# LTE_UART_USB_adapter.net
KiCad netlist of a schematic drawn in Altium Designer
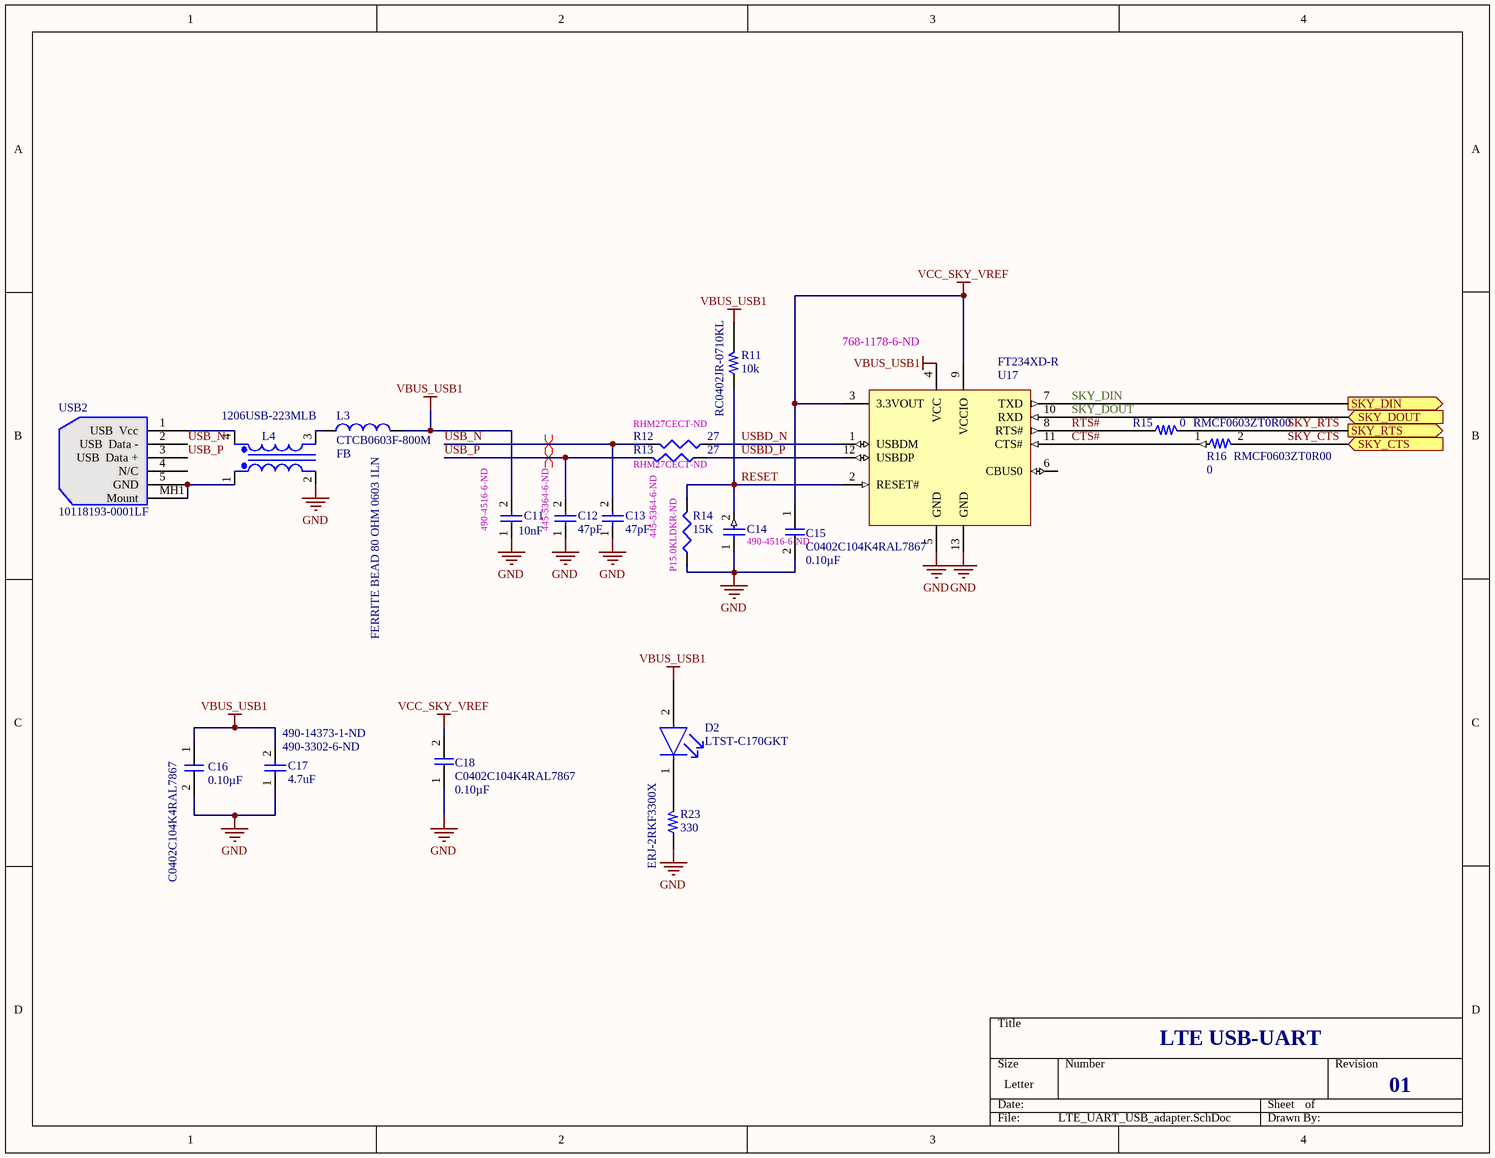
[diagram p0: LTE_UART_USB_adapter.SchDoc]

(export (version "E")
  (design (tool "Eeschema 10.0.6"))
  (components
    (comp (ref "C11")
      (value "GRM155R71H103KA88D")
      (footprint "SMD CAP 1005")
      (description "10000 pF ±10% 50V Ceramic Capacitor X7R 0402 (1005 Metric)")
      (fields
        (field (name "CAPACITANCE") "10nF")
        (field (name "DIGI-KEY PART NUMBER") "490-4516-1-ND")
        (field (name "MANUFACTURER") "Murata Electronics North America")
        (field (name "SUPPLIER PART NUMBER 1") "490-4516-6-ND")
      )
      (libsource (lib "TempProbe") (part "Cap Semi"))
    )
    (comp (ref "C12")
      (value "C1005C0G1H470G050BA")
      (footprint "SMD CAP 1005")
      (description "47 pF ±2% 50V Ceramic Capacitor C0G, NP0 0402 (1005 Metric)")
      (fields
        (field (name "CAPACITANCE") "47pF")
        (field (name "DIGI-KEY PART NUMBER") "445-5364-1-ND")
        (field (name "MANUFACTURER") "TDK Corporation")
        (field (name "SUPPLIER PART NUMBER 1") "445-5364-6-ND")
      )
      (libsource (lib "TempProbe") (part "Cap Semi"))
    )
    (comp (ref "C13")
      (value "C1005C0G1H470G050BA")
      (footprint "SMD CAP 1005")
      (description "47 pF ±2% 50V Ceramic Capacitor C0G, NP0 0402 (1005 Metric)")
      (fields
        (field (name "CAPACITANCE") "47pF")
        (field (name "DIGI-KEY PART NUMBER") "445-5364-1-ND")
        (field (name "MANUFACTURER") "TDK Corporation")
        (field (name "SUPPLIER PART NUMBER 1") "445-5364-6-ND")
      )
      (libsource (lib "TempProbe") (part "Cap Semi"))
    )
    (comp (ref "C14")
      (value "GRM155R71H103KA88D")
      (footprint "SMD CAP 1005")
      (description "10000 pF ±10% 50V Ceramic Capacitor X7R 0402 (1005 Metric)")
      (fields
        (field (name "DIGI-KEY PART NUMBER") "490-4516-1-ND")
        (field (name "MANUFACTURER") "Murata Electronics North America")
        (field (name "SUPPLIER PART NUMBER 1") "490-4516-6-ND")
      )
      (libsource (lib "TempProbe") (part "Cap Semi"))
    )
    (comp (ref "C15")
      (value "C0402C104K4RAL7867")
      (footprint "Passives:SMD CAP 1005")
      (description "0.1 µF ±10% 16V Ceramic Capacitor X7R 0402 (1005 Metric)")
      (fields
        (field (name "TOLERANCE") "±10%")
        (field (name "CAPACITANCE") "0.10µF")
        (field (name "PART_NUMBER") "1000742")
      )
      (libsource (lib "AltiumProductionDatabase") (part "C, 0.1 uF, 16V, 10%, X7R, 0402 CER"))
    )
    (comp (ref "C16")
      (value "C0402C104K4RAL7867")
      (footprint "Passives:SMD CAP 1005")
      (description "0.1 µF ±10% 16V Ceramic Capacitor X7R 0402 (1005 Metric)")
      (fields
        (field (name "TOLERANCE") "±10%")
        (field (name "CAPACITANCE") "0.10µF")
        (field (name "PART_NUMBER") "1000742")
      )
      (libsource (lib "AltiumProductionDatabase") (part "C, 0.1 uF, 16V, 10%, X7R, 0402 CER"))
    )
    (comp (ref "C17")
      (value "GRM188R61A475KAAJD")
      (footprint "CAPC1608M")
      (description "4.7 µF ±10% 10V Ceramic Capacitor X5R 0603 (1608 Metric)")
      (fields
        (field (name "CAPACITANCE") "4.7uF")
        (field (name "DIGI-KEY PART NUMBER") "490-14373-1-ND")
        (field (name "MANUFACTURER") "Murata Electronics North America")
        (field (name "SUPPLIER PART NUMBER 1") "490-3302-6-ND")
        (field (name "SUPPLIER PART NUMBER 2") "490-14373-1-ND")
      )
      (libsource (lib "TempProbe") (part "Cap Semi"))
    )
    (comp (ref "C18")
      (value "C0402C104K4RAL7867")
      (footprint "Passives:SMD CAP 1005")
      (description "0.1 µF ±10% 16V Ceramic Capacitor X7R 0402 (1005 Metric)")
      (fields
        (field (name "TOLERANCE") "±10%")
        (field (name "CAPACITANCE") "0.10µF")
        (field (name "PART_NUMBER") "1000742")
      )
      (libsource (lib "AltiumProductionDatabase") (part "C, 0.1 uF, 16V, 10%, X7R, 0402 CER"))
    )
    (comp (ref "D2")
      (value "LTST-C170GKT")
      (footprint "FP-LTST-C170GKT-MFG")
      (description "Green 569nm LED Indication - Discrete 2.1V 0805 (2012 Metric)")
      (fields (field (name "VOLTAGE") "5V") (field (name "DIGI-KEY PART NUMBER") "160-1179-1-ND"))
      (libsource (lib "Altium Content Vault") (part "8706943c75ba83719d021d2fdc84c58"))
    )
    (comp (ref "L3")
      (value "CTCB0603F-800M")
      (footprint "INDC1608M")
      (description "80 Ohms @ 100 MHz 1 Ferrite Bead 0603 (1608 Metric) 600mA 100mOhm")
      (fields
        (field (name "ALTIUM_VALUE") "FB")
        (field (name "DIGI-KEY PART NUMBER") "4161-CTCB0603F-800M-ND")
        (field (name "MANUFACTURER") "Central Technologies")
        (field (name "DESC") "FERRITE BEAD 80 OHM 0603 1LN")
        (field (name "PUBLISHER") "Altium Limited")
      )
      (libsource (lib "Miscellaneous Devices") (part "Inductor"))
    )
    (comp (ref "L4")
      (value "1206USB-223MLB")
      (footprint "1206USB-223MLB")
      (description "Common Mode Chokes / Filters")
      (fields (field (name "MANUFACTURER") "Coilcraft") (field (name "PUBLISHER") "Altium Limited"))
      (libsource (lib "Miscellaneous Devices") (part "Trans Ideal"))
    )
    (comp (ref "R11")
      (value "RC0402JR-0710KL")
      (footprint "SMD RES 1005")
      (description "10 kOhms ±5% 0.063W, 1/16W Chip Resistor 0402 (1005 Metric) Moisture Resistant Thick Film")
      (fields
        (field (name "PART_NUMBER") "RC0402JR-0710KL")
        (field (name "RESISTANCE_OHMS") "10k")
        (field (name "POWER") "0.063W, 1/16W")
        (field (name "TOLERANCE") "±1%")
      )
      (libsource (lib "AltiumProductionDatabase") (part "R, 10K, 1%, 1/16W,  0402"))
    )
    (comp (ref "R12")
      (value "27")
      (footprint "SMD RES 1005")
      (description "RES SMD 27 OHM 5% 1/16W 0402")
      (fields
        (field (name "DIGI-KEY PART NUMBER") "RHM27CECT-ND")
        (field (name "MANUFACTURER") "Rohm Semiconductor")
        (field (name "SUPPLIER PART NUMBER 1") "RHM27CECT-ND")
        (field (name "PUBLISHER") "Altium Limited")
      )
      (libsource (lib "Miscellaneous Devices") (part "Res3"))
    )
    (comp (ref "R13")
      (value "27")
      (footprint "SMD RES 1005")
      (description "RES SMD 27 OHM 5% 1/16W 0402")
      (fields
        (field (name "DIGI-KEY PART NUMBER") "RHM27CECT-ND")
        (field (name "MANUFACTURER") "Rohm Semiconductor")
        (field (name "SUPPLIER PART NUMBER 1") "RHM27CECT-ND")
        (field (name "PUBLISHER") "Altium Limited")
      )
      (libsource (lib "Miscellaneous Devices") (part "Res3"))
    )
    (comp (ref "R14")
      (value "15K")
      (footprint "SMD RES 1005")
      (description "RES SMD 15K OHM 1% 1/10W 0402")
      (fields
        (field (name "DIGI-KEY PART NUMBER") "P15.0KLCT-ND")
        (field (name "MANUFACTURER") "Panasonic Electronic Components")
        (field (name "SUPPLIER PART NUMBER 1") "P15.0KLDKR-ND")
        (field (name "PUBLISHER") "Altium Limited")
      )
      (libsource (lib "Miscellaneous Devices") (part "Res3"))
    )
    (comp (ref "R15")
      (value "RMCF0603ZT0R00")
      (footprint "RESC1608M")
      (description "0 Ohms Jumper Chip Resistor 0603 (1608 Metric) Automotive AEC-Q200 Thick Film")
      (fields
        (field (name "PART_NUMBER") "RMCF0603ZT0R00")
        (field (name "RESISTANCE") "0")
        (field (name "POWER") "0.25W, 1/4W")
        (field (name "TOLERANCE") "±1%")
      )
      (libsource (lib "") (part "R, 0.1, 1%, 1/4W, 0603_1"))
    )
    (comp (ref "R16")
      (value "RMCF0603ZT0R00")
      (footprint "RESC1608M")
      (description "0 Ohms Jumper Chip Resistor 0603 (1608 Metric) Automotive AEC-Q200 Thick Film")
      (fields
        (field (name "PART_NUMBER") "RMCF0603ZT0R00")
        (field (name "RESISTANCE") "0")
        (field (name "POWER") "0.25W, 1/4W")
        (field (name "TOLERANCE") "±1%")
      )
      (libsource (lib "AltiumProductionDatabase") (part "R, 0.1, 1%, 1/4W, 0603"))
    )
    (comp (ref "R23")
      (value "ERJ-2RKF3300X")
      (footprint "SMD RES 1005")
      (description "330 Ohms ±1% 0.1W, 1/10W Chip Resistor 0402 (1005 Metric) Automotive AEC-Q200 Thick Film")
      (fields
        (field (name "PART_NUMBER") "1001162")
        (field (name "RESISTANCE") "330")
        (field (name "POWER") "0.1W, 1/10W")
      )
      (libsource (lib "AltiumProductionDatabase") (part "R, 330, 1%, 1/10W, 0402"))
    )
    (comp (ref "U17")
      (value "FT234XD-R")
      (footprint "DFN-12_V")
      (description "IC USB SERIAL BASIC UART 12DFN")
      (fields
        (field (name "MANUFACTURER") "FTDI, Future Technology Devices International Ltd")
        (field (name "DIGI-KEY PART NUMBER") "768-1178-1-ND")
        (field (name "SUPPLIER PART NUMBER 1") "768-1178-6-ND")
      )
      (libsource (lib "Altium Content Vault") (part "CMP-0248-00027-1"))
    )
    (comp (ref "USB2")
      (value "10118193-0001LF")
      (footprint "10118193-0001LF Rev01")
      (description "USB - micro B USB 2.0 Receptacle Connector 5 Position Surface Mount, Right Angle, Horizontal")
      (fields (field (name "MANUFACTURER") "FCI") (field (name "DIGI-KEY PART NUMBER") "609-4616-1-ND"))
      (libsource (lib "USB") (part "USB mini"))
    )
  )
  (nets
    (net (code "1") (name "/CTS#") (class "Default")
      (node (ref "R16") (pin "1") (pinfunction "1_1") (pintype "output"))
      (node (ref "U17") (pin "11") (pinfunction "CTS#_11") (pintype "input"))
    )
    (net (code "2") (name "/RESET") (class "Default")
      (node (ref "C14") (pin "2") (pinfunction "2_2") (pintype "passive"))
      (node (ref "R11") (pin "1") (pinfunction "1_1") (pintype "passive"))
      (node (ref "R14") (pin "2") (pinfunction "2_2") (pintype "passive"))
      (node (ref "U17") (pin "2") (pinfunction "RESET#_2") (pintype "input"))
    )
    (net (code "3") (name "/RTS#") (class "Default")
      (node (ref "R15") (pin "1") (pinfunction "1_1") (pintype "passive"))
      (node (ref "U17") (pin "8") (pinfunction "RTS#_8") (pintype "output"))
    )
    (net (code "4") (name "/SKY_CTS") (class "Default")
      (node (ref "R16") (pin "2") (pinfunction "2_2") (pintype "passive"))
    )
    (net (code "5") (name "/SKY_DIN") (class "Default")
      (node (ref "U17") (pin "7") (pinfunction "TXD_7") (pintype "output"))
    )
    (net (code "6") (name "/SKY_DOUT") (class "Default")
      (node (ref "U17") (pin "10") (pinfunction "RXD_10") (pintype "input"))
    )
    (net (code "7") (name "/SKY_RTS") (class "Default")
      (node (ref "R15") (pin "2") (pinfunction "2_2") (pintype "passive"))
    )
    (net (code "8") (name "/USBD_N") (class "Default")
      (node (ref "R12") (pin "1") (pinfunction "1_1") (pintype "passive"))
      (node (ref "U17") (pin "1") (pinfunction "USBDM_1") (pintype "bidirectional"))
    )
    (net (code "9") (name "/USBD_P") (class "Default")
      (node (ref "R13") (pin "1") (pinfunction "1_1") (pintype "passive"))
      (node (ref "U17") (pin "12") (pinfunction "USBDP_12") (pintype "bidirectional"))
    )
    (net (code "10") (name "/USB_N") (class "Default")
      (node (ref "C13") (pin "2") (pinfunction "2_2") (pintype "passive"))
      (node (ref "R12") (pin "2") (pinfunction "2_2") (pintype "passive"))
      (node (ref "USB2") (pin "2") (pinfunction "USB__Data_-_2") (pintype "passive"))
    )
    (net (code "11") (name "/USB_P") (class "Default")
      (node (ref "C12") (pin "2") (pinfunction "2_2") (pintype "passive"))
      (node (ref "R13") (pin "2") (pinfunction "2_2") (pintype "passive"))
      (node (ref "USB2") (pin "3") (pinfunction "USB__Data_+_3") (pintype "passive"))
    )
    (net (code "12") (name "GND") (class "Default")
      (node (ref "C11") (pin "1") (pinfunction "1_1") (pintype "passive"))
      (node (ref "C12") (pin "1") (pinfunction "1_1") (pintype "passive"))
      (node (ref "C13") (pin "1") (pinfunction "1_1") (pintype "passive"))
      (node (ref "C14") (pin "1") (pinfunction "1_1") (pintype "passive"))
      (node (ref "C15") (pin "2") (pinfunction "2_2") (pintype "passive"))
      (node (ref "C16") (pin "2") (pinfunction "2_2") (pintype "passive"))
      (node (ref "C17") (pin "1") (pinfunction "1_1") (pintype "passive"))
      (node (ref "C18") (pin "1") (pinfunction "1_1") (pintype "passive"))
      (node (ref "L4") (pin "2") (pinfunction "Pri-_2") (pintype "passive"))
      (node (ref "R14") (pin "1") (pinfunction "1_1") (pintype "passive"))
      (node (ref "R23") (pin "1") (pinfunction "1_1") (pintype "passive"))
      (node (ref "U17") (pin "13") (pinfunction "GND_13") (pintype "power_in"))
      (node (ref "U17") (pin "5") (pinfunction "GND_5") (pintype "power_in"))
    )
    (net (code "13") (name "Net-(D2-C)") (class "Default")
      (node (ref "D2") (pin "1") (pinfunction "C_1") (pintype "passive"))
      (node (ref "R23") (pin "2") (pinfunction "2_2") (pintype "passive"))
    )
    (net (code "14") (name "Net-(L4-Pri+)") (class "Default")
      (node (ref "L4") (pin "1") (pinfunction "Pri+_1") (pintype "passive"))
      (node (ref "USB2") (pin "5") (pinfunction "GND_5") (pintype "passive"))
      (node (ref "USB2") (pin "MH1") (pinfunction "Mount_MH1") (pintype "passive"))
    )
    (net (code "15") (name "Net-(L4-Sec+)") (class "Default")
      (node (ref "L4") (pin "4") (pinfunction "Sec+_4") (pintype "passive"))
      (node (ref "USB2") (pin "1") (pinfunction "USB__Vcc_1") (pintype "passive"))
    )
    (net (code "16") (name "Net-(L4-Sec-)") (class "Default")
      (node (ref "L3") (pin "2") (pinfunction "2_2") (pintype "passive"))
      (node (ref "L4") (pin "3") (pinfunction "Sec-_3") (pintype "passive"))
    )
    (net (code "17") (name "VBUS_USB1") (class "Default")
      (node (ref "C11") (pin "2") (pinfunction "2_2") (pintype "passive"))
      (node (ref "C16") (pin "1") (pinfunction "1_1") (pintype "passive"))
      (node (ref "C17") (pin "2") (pinfunction "2_2") (pintype "passive"))
      (node (ref "D2") (pin "2") (pinfunction "A_2") (pintype "passive"))
      (node (ref "L3") (pin "1") (pinfunction "1_1") (pintype "passive"))
      (node (ref "R11") (pin "2") (pinfunction "2_2") (pintype "passive"))
      (node (ref "U17") (pin "4") (pinfunction "VCC_4") (pintype "power_in"))
    )
    (net (code "18") (name "VCC_SKY_VREF") (class "Default")
      (node (ref "C15") (pin "1") (pinfunction "1_1") (pintype "passive"))
      (node (ref "C18") (pin "2") (pinfunction "2_2") (pintype "passive"))
      (node (ref "U17") (pin "3") (pinfunction "3.3VOUT_3") (pintype "power_in"))
      (node (ref "U17") (pin "9") (pinfunction "VCCIO_9") (pintype "power_in"))
    )
    (net (code "19") (name "unconnected-(U17-CBUS0-Pad6)") (class "Default")
      (node (ref "U17") (pin "6") (pinfunction "CBUS0_6") (pintype "bidirectional"))
    )
    (net (code "20") (name "unconnected-(USB2-N{slash}C-Pad4)") (class "Default")
      (node (ref "USB2") (pin "4") (pinfunction "N/C_4") (pintype "passive"))
    )
  )
)
